# MCU.net
KiCad netlist of a schematic drawn in Altium Designer
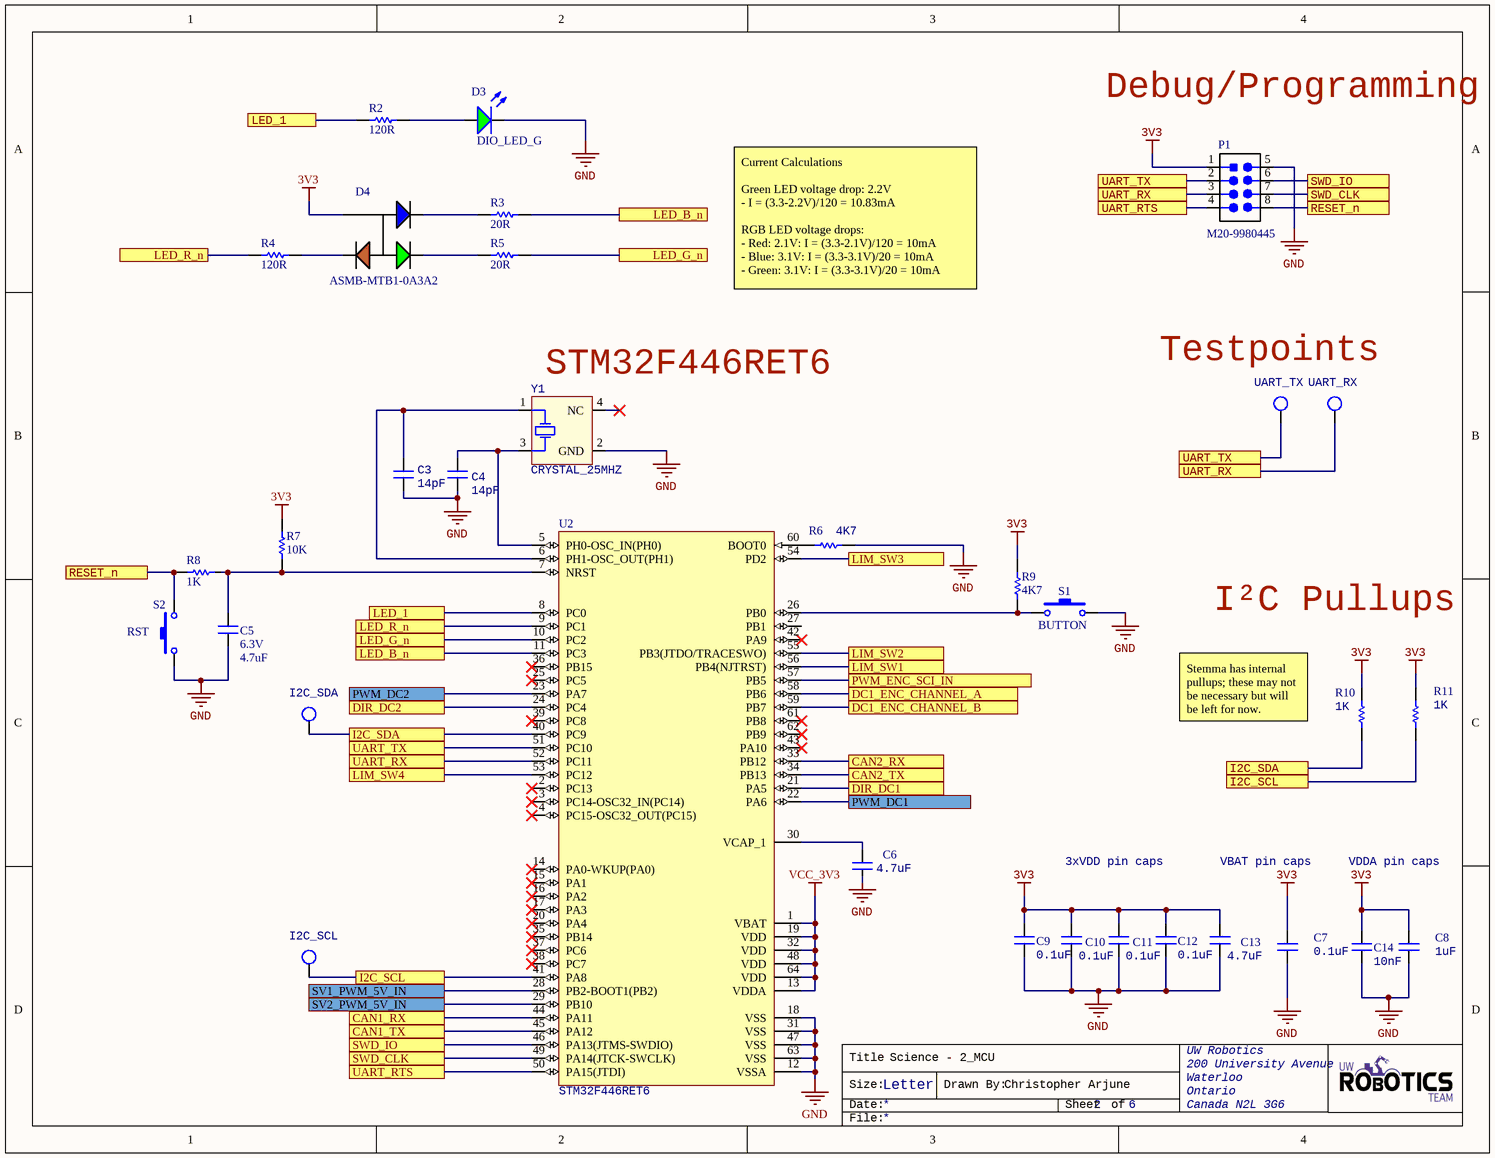
[diagram p0: MCU.SchDoc]

(export (version "E")
  (design (tool "Eeschema 10.0.6"))
  (components
    (comp (ref "C3")
      (value "14pF")
      (description "CAP CER 14PF 50V C0G/NP0 0603")
      (fields (field (name "TOLERANCE") "5%") (field (name "Comment") "CAP_14pF_50V_0603"))
      (libsource (lib "UWRT_Schematic_Library_2020") (part "CAP_14pF_50V_0603"))
    )
    (comp (ref "C4")
      (value "14pF")
      (description "CAP CER 14PF 50V C0G/NP0 0603")
      (fields (field (name "TOLERANCE") "5%") (field (name "Comment") "CAP_14pF_50V_0603"))
      (libsource (lib "UWRT_Schematic_Library_2020") (part "CAP_14pF_50V_0603"))
    )
    (comp (ref "C5")
      (value "4.7uF")
      (footprint "CAPC0603(1608)55_N")
      (description "CAP CER 4.7UF 6.3V X5R 0603")
      (fields (field (name "VOLTAGE RATING") "6.3V") (field (name "Comment") "CAP_4.7uF_0603"))
      (libsource (lib "UWRT_Schematic_Library_2020") (part "CAP_4.7uF_0603"))
    )
    (comp (ref "C6")
      (value "4.7uF")
      (footprint "CAPC0603(1608)55_N")
      (description "CAP CER 4.7UF 6.3V X5R 0603")
      (fields (field (name "MANUFACTURER") "Yageo") (field (name "MPN") "CC0603KRX5R5BB475"))
      (libsource (lib "UWRT_Schematic_Library_2020") (part "CAP_4.7uF_0603"))
    )
    (comp (ref "C7")
      (value "0.1uF")
      (footprint "CAPC0603(1608)55_N")
      (description "CAP CER 0.1UF 16V X7R 0603")
      (fields (field (name "MANUFACTURER") "Yageo") (field (name "MPN") "CC0603KRX7R7BB104"))
      (libsource (lib "UWRT_Schematic_Library_2020") (part "CAP_0.1uF_16V_0603"))
    )
    (comp (ref "C8")
      (value "1uF")
      (footprint "CAPC0603(1608)55_N")
      (description "CAP CER 1UF 16V Y5V 0603")
      (fields (field (name "MANUFACTURER") "Yageo") (field (name "MPN") "CC0603ZRY5V7BB105"))
      (libsource (lib "UWRT_Schematic_Library_2020") (part "CAP_1uF_16V_0603"))
    )
    (comp (ref "C9")
      (value "0.1uF")
      (footprint "CAPC0603(1608)55_N")
      (description "CAP CER 0.1UF 16V X7R 0603")
      (fields (field (name "MANUFACTURER") "Yageo") (field (name "MPN") "CC0603KRX7R7BB104"))
      (libsource (lib "UWRT_Schematic_Library_2020") (part "CAP_0.1uF_16V_0603"))
    )
    (comp (ref "C10")
      (value "0.1uF")
      (footprint "CAPC0603(1608)55_N")
      (description "CAP CER 0.1UF 16V X7R 0603")
      (fields (field (name "MANUFACTURER") "Yageo") (field (name "MPN") "CC0603KRX7R7BB104"))
      (libsource (lib "UWRT_Schematic_Library_2020") (part "CAP_0.1uF_16V_0603"))
    )
    (comp (ref "C11")
      (value "0.1uF")
      (footprint "CAPC0603(1608)55_N")
      (description "CAP CER 0.1UF 16V X7R 0603")
      (fields (field (name "MANUFACTURER") "Yageo") (field (name "MPN") "CC0603KRX7R7BB104"))
      (libsource (lib "UWRT_Schematic_Library_2020") (part "CAP_0.1uF_16V_0603"))
    )
    (comp (ref "C12")
      (value "0.1uF")
      (footprint "CAPC0603(1608)55_N")
      (description "CAP CER 0.1UF 16V X7R 0603")
      (fields (field (name "MANUFACTURER") "Yageo") (field (name "MPN") "CC0603KRX7R7BB104"))
      (libsource (lib "UWRT_Schematic_Library_2020") (part "CAP_0.1uF_16V_0603"))
    )
    (comp (ref "C13")
      (value "4.7uF")
      (footprint "CAPC0603(1608)55_N")
      (description "CAP CER 4.7UF 6.3V X5R 0603")
      (fields (field (name "MANUFACTURER") "Yageo") (field (name "MPN") "CC0603KRX5R5BB475"))
      (libsource (lib "UWRT_Schematic_Library_2020") (part "CAP_4.7uF_0603"))
    )
    (comp (ref "C14")
      (value "10nF")
      (footprint "CAPC0603(1608)55_N")
      (description "CAP CER 10000PF 16V X7R 0603")
      (fields (field (name "MANUFACTURER") "Yageo") (field (name "MPN") "CC0603KRX7R7BB103"))
      (libsource (lib "UWRT_Schematic_Library_2020") (part "CAP_10nF_0603"))
    )
    (comp (ref "D3")
      (value "DIO_LED_G")
      (footprint "LED_0805_LINE")
      (description "LED GREEN DIFFUSED 0805 SMD")
      (fields (field (name "MANUFACTURER") "OSRAM") (field (name "MPN") "LG R971-KN-1"))
      (libsource (lib "UWRT_Schematic_Library_2020") (part "DIO_LED_G"))
    )
    (comp (ref "D4")
      (value "LED_RGB")
      (footprint "LED_RGB")
      (description "LED RGB DIFFUSED 4PLCC SMD")
      (fields (field (name "MANUFACTURER PART NUMBER 1") "ASMB-MTB1-0A3A2"))
      (libsource (lib "UWRT_Schematic_Library_2020") (part "LED_RGB"))
    )
    (comp (ref "I2C_SCL")
      (value "TESTPOINT_LOOP")
      (footprint "TESTPOINT_LOOP")
      (description "Loop testpoint through-hole pad")
      (fields (field (name "MANUFACTURER") "Keystone Electronics"))
      (libsource (lib "UWRT_Schematic_Library_2020") (part "TESTPOINT_LOOP"))
    )
    (comp (ref "I2C_SDA")
      (value "TESTPOINT_LOOP")
      (footprint "TESTPOINT_LOOP")
      (description "Loop testpoint through-hole pad")
      (fields (field (name "MANUFACTURER") "Keystone Electronics"))
      (libsource (lib "UWRT_Schematic_Library_2020") (part "TESTPOINT_LOOP"))
    )
    (comp (ref "P1")
      (value "HEADER 4X2")
      (footprint "HEADER_2X4")
      (description "CONN HEADER VERT 8POS 2.54MM")
      (fields (field (name "MANUFACTURER PART NUMBER 1") "M20-9980445"))
      (libsource (lib "UWRT_Schematic_Library_2020") (part "HEADER 4X2"))
    )
    (comp (ref "R2")
      (value "120R")
      (footprint "RESC0603(1608)_N")
      (description "RES SMD 120 OHM 5% 1/10W 0603")
      (fields (field (name "MANUFACTURER") "Yageo") (field (name "TOLERANCE") "5%"))
      (libsource (lib "UWRT_Schematic_Library_2020") (part "RES_120R_0603"))
    )
    (comp (ref "R3")
      (value "20R")
      (footprint "RESC0603(1608)_N")
      (description "RES SMD 20 OHM 5% 1/10W 0603")
      (fields (field (name "MANUFACTURER") "Yageo") (field (name "MPN") "RC0603JR-0720RL"))
      (libsource (lib "UWRT_Schematic_Library_2020") (part "RES_20R_0603"))
    )
    (comp (ref "R4")
      (value "120R")
      (footprint "RESC0603(1608)_N")
      (description "RES SMD 120 OHM 5% 1/10W 0603")
      (fields (field (name "MANUFACTURER") "Yageo") (field (name "MPN") "RC0603JR-07120RL"))
      (libsource (lib "UWRT_Schematic_Library_2020") (part "RES_120R_0603"))
    )
    (comp (ref "R5")
      (value "20R")
      (footprint "RESC0603(1608)_N")
      (description "RES SMD 20 OHM 5% 1/10W 0603")
      (fields (field (name "MANUFACTURER") "Yageo") (field (name "MPN") "RC0603JR-0720RL"))
      (libsource (lib "UWRT_Schematic_Library_2020") (part "RES_20R_0603"))
    )
    (comp (ref "R6")
      (value "4K7")
      (footprint "RESC0603(1608)_N")
      (description "RES SMD 4.7K OHM 5% 1/10W 0603")
      (fields (field (name "MANUFACTURER") "Yageo") (field (name "TOLERANCE") "5%"))
      (libsource (lib "UWRT_Schematic_Library_2020") (part "RES_4K7_0603"))
    )
    (comp (ref "R7")
      (value "10K")
      (footprint "RESC0603(1608)_N")
      (description "RES SMD 10K OHM 5% 1/10W 0603")
      (fields (field (name "TOLERANCE") "5%") (field (name "Comment") "RES_10K_0603"))
      (libsource (lib "UWRT_Schematic_Library_2020") (part "RES_10K_0603"))
    )
    (comp (ref "R8")
      (value "1K")
      (footprint "RESC0603(1608)_N")
      (description "RES SMD 1K OHM 5% 1/10W 0603")
      (fields (field (name "TOLERANCE") "5%") (field (name "Comment") "RES_1K_0603"))
      (libsource (lib "UWRT_Schematic_Library_2020") (part "RES_1K_0603"))
    )
    (comp (ref "R9")
      (value "4K7")
      (footprint "RESC0603(1608)_N")
      (description "RES SMD 4.7K OHM 5% 1/10W 0603")
      (fields (field (name "MANUFACTURER") "Yageo") (field (name "TOLERANCE") "5%"))
      (libsource (lib "UWRT_Schematic_Library_2020") (part "RES_4K7_0603"))
    )
    (comp (ref "R10")
      (value "1K")
      (footprint "RESC0603(1608)_N")
      (description "RES SMD 4.7K OHM 5% 1/10W 0603")
      (fields (field (name "MANUFACTURER") "Yageo") (field (name "TOLERANCE") "5%"))
      (libsource (lib "UWRT_Schematic_Library_2020") (part "RES_4K7_0603"))
    )
    (comp (ref "R11")
      (value "1K")
      (footprint "RESC0603(1608)_N")
      (description "RES SMD 4.7K OHM 5% 1/10W 0603")
      (fields (field (name "MANUFACTURER") "Yageo") (field (name "TOLERANCE") "5%"))
      (libsource (lib "UWRT_Schematic_Library_2020") (part "RES_4K7_0603"))
    )
    (comp (ref "S1")
      (value "BUTTON")
      (footprint "B3U-1100P")
      (description "Tactile Switch (Grey)")
      (fields (field (name "MPN") "B3U-1100P") (field (name "MANUFACTURER") "Omron Electronics Inc-EMC Div"))
      (libsource (lib "UWRT_Schematic_Library_2020") (part "SW_TACTILE"))
    )
    (comp (ref "S2")
      (value "RST")
      (footprint "PTS830GM140")
      (description "Power Switch (Red)")
      (fields (field (name "MPN") "PTS830GM140 SMTR LFS") (field (name "MANUFACTURER") "C&K"))
      (libsource (lib "UWRT_Schematic_Library_2020") (part "SW_PWR"))
    )
    (comp (ref "U2")
      (value "STM32F446RET6")
      (footprint "STM-LQFP64_L")
      (libsource (lib "UWRT_Schematic_Library_2020") (part "MCU_STM32F446RET6"))
    )
    (comp (ref "UART_RX")
      (value "TESTPOINT_LOOP")
      (footprint "TESTPOINT_LOOP")
      (description "Loop testpoint through-hole pad")
      (fields (field (name "MANUFACTURER") "Keystone Electronics"))
      (libsource (lib "UWRT_Schematic_Library_2020") (part "TESTPOINT_LOOP"))
    )
    (comp (ref "UART_TX")
      (value "TESTPOINT_LOOP")
      (footprint "TESTPOINT_LOOP")
      (description "Loop testpoint through-hole pad")
      (fields (field (name "MANUFACTURER") "Keystone Electronics"))
      (libsource (lib "UWRT_Schematic_Library_2020") (part "TESTPOINT_LOOP"))
    )
    (comp (ref "Y1")
      (value "CRYSTAL_25MHZ")
      (description "CRYSTAL 25.0000MHZ 12PF SMD")
      (libsource (lib "UWRT_Schematic_Library_2020") (part "CRYSTAL_25MHZ"))
    )
  )
  (nets
    (net (code "1") (name "/CAN1_RX") (class "Default")
      (node (ref "U2") (pin "44") (pinfunction "PA11_44") (pintype "bidirectional"))
    )
    (net (code "2") (name "/CAN1_TX") (class "Default")
      (node (ref "U2") (pin "45") (pinfunction "PA12_45") (pintype "bidirectional"))
    )
    (net (code "3") (name "/CAN2_RX") (class "Default")
      (node (ref "U2") (pin "33") (pinfunction "PB12_33") (pintype "bidirectional"))
    )
    (net (code "4") (name "/CAN2_TX") (class "Default")
      (node (ref "U2") (pin "34") (pinfunction "PB13_34") (pintype "bidirectional"))
    )
    (net (code "5") (name "/DC1_ENC_CHANNEL_A") (class "Default")
      (node (ref "U2") (pin "58") (pinfunction "PB6_58") (pintype "bidirectional"))
    )
    (net (code "6") (name "/DC1_ENC_CHANNEL_B") (class "Default")
      (node (ref "U2") (pin "59") (pinfunction "PB7_59") (pintype "bidirectional"))
    )
    (net (code "7") (name "/DIR_DC1") (class "Default")
      (node (ref "U2") (pin "21") (pinfunction "PA5_21") (pintype "bidirectional"))
    )
    (net (code "8") (name "/DIR_DC2") (class "Default")
      (node (ref "U2") (pin "24") (pinfunction "PC4_24") (pintype "bidirectional"))
    )
    (net (code "9") (name "/I2C_SCL") (class "Default")
      (node (ref "I2C_SCL") (pin "1") (pintype "passive"))
      (node (ref "R11") (pin "1") (pinfunction "1_1") (pintype "passive"))
      (node (ref "U2") (pin "41") (pinfunction "PA8_41") (pintype "bidirectional"))
    )
    (net (code "10") (name "/I2C_SDA") (class "Default")
      (node (ref "I2C_SDA") (pin "1") (pintype "passive"))
      (node (ref "R10") (pin "1") (pinfunction "1_1") (pintype "passive"))
      (node (ref "U2") (pin "40") (pinfunction "PC9_40") (pintype "bidirectional"))
    )
    (net (code "11") (name "/LED_1") (class "Default")
      (node (ref "R2") (pin "1") (pinfunction "1_1") (pintype "passive"))
      (node (ref "U2") (pin "8") (pinfunction "PC0_8") (pintype "bidirectional"))
    )
    (net (code "12") (name "/LED_B_n") (class "Default")
      (node (ref "R3") (pin "2") (pinfunction "2_2") (pintype "passive"))
      (node (ref "U2") (pin "11") (pinfunction "PC3_11") (pintype "bidirectional"))
    )
    (net (code "13") (name "/LED_G_n") (class "Default")
      (node (ref "R5") (pin "2") (pinfunction "2_2") (pintype "passive"))
      (node (ref "U2") (pin "10") (pinfunction "PC2_10") (pintype "bidirectional"))
    )
    (net (code "14") (name "/LED_R_n") (class "Default")
      (node (ref "R4") (pin "1") (pinfunction "1_1") (pintype "passive"))
      (node (ref "U2") (pin "9") (pinfunction "PC1_9") (pintype "bidirectional"))
    )
    (net (code "15") (name "/LIM_SW1") (class "Default")
      (node (ref "U2") (pin "56") (pinfunction "PB4(NJTRST)_56") (pintype "bidirectional"))
    )
    (net (code "16") (name "/LIM_SW2") (class "Default")
      (node (ref "U2") (pin "55") (pinfunction "PB3(JTDO/TRACESWO)_55") (pintype "bidirectional"))
    )
    (net (code "17") (name "/LIM_SW3") (class "Default")
      (node (ref "U2") (pin "54") (pinfunction "PD2_54") (pintype "bidirectional"))
    )
    (net (code "18") (name "/LIM_SW4") (class "Default")
      (node (ref "U2") (pin "53") (pinfunction "PC12_53") (pintype "bidirectional"))
    )
    (net (code "19") (name "/PWM_DC1") (class "Default")
      (node (ref "U2") (pin "22") (pinfunction "PA6_22") (pintype "bidirectional"))
    )
    (net (code "20") (name "/PWM_DC2") (class "Default")
      (node (ref "U2") (pin "23") (pinfunction "PA7_23") (pintype "bidirectional"))
    )
    (net (code "21") (name "/PWM_ENC_SCI_IN") (class "Default")
      (node (ref "U2") (pin "57") (pinfunction "PB5_57") (pintype "bidirectional"))
    )
    (net (code "22") (name "/RESET_n") (class "Default")
      (node (ref "P1") (pin "8") (pinfunction "4_8") (pintype "passive"))
      (node (ref "R8") (pin "1") (pinfunction "1_1") (pintype "passive"))
      (node (ref "S2") (pin "2") (pinfunction "2_2") (pintype "passive"))
    )
    (net (code "23") (name "/SV1_PWM_5V_IN") (class "Default")
      (node (ref "U2") (pin "28") (pinfunction "PB2-BOOT1(PB2)_28") (pintype "bidirectional"))
    )
    (net (code "24") (name "/SV2_PWM_5V_IN") (class "Default")
      (node (ref "U2") (pin "29") (pinfunction "PB10_29") (pintype "bidirectional"))
    )
    (net (code "25") (name "/SWD_CLK") (class "Default")
      (node (ref "P1") (pin "7") (pinfunction "3_7") (pintype "passive"))
      (node (ref "U2") (pin "49") (pinfunction "PA14(JTCK-SWCLK)_49") (pintype "bidirectional"))
    )
    (net (code "26") (name "/SWD_IO") (class "Default")
      (node (ref "P1") (pin "6") (pinfunction "2_6") (pintype "passive"))
      (node (ref "U2") (pin "46") (pinfunction "PA13(JTMS-SWDIO)_46") (pintype "bidirectional"))
    )
    (net (code "27") (name "/UART_RTS") (class "Default")
      (node (ref "P1") (pin "4") (pinfunction "4_4") (pintype "passive"))
      (node (ref "U2") (pin "50") (pinfunction "PA15(JTDI)_50") (pintype "bidirectional"))
    )
    (net (code "28") (name "/UART_RX") (class "Default")
      (node (ref "P1") (pin "3") (pinfunction "3_3") (pintype "passive"))
      (node (ref "U2") (pin "52") (pinfunction "PC11_52") (pintype "bidirectional"))
      (node (ref "UART_RX") (pin "1") (pintype "passive"))
    )
    (net (code "29") (name "/UART_TX") (class "Default")
      (node (ref "P1") (pin "2") (pinfunction "2_2") (pintype "passive"))
      (node (ref "U2") (pin "51") (pinfunction "PC10_51") (pintype "bidirectional"))
      (node (ref "UART_TX") (pin "1") (pintype "passive"))
    )
    (net (code "30") (name "3V3") (class "Default")
      (node (ref "C10") (pin "2") (pinfunction "2_2") (pintype "passive"))
      (node (ref "C11") (pin "2") (pinfunction "2_2") (pintype "passive"))
      (node (ref "C12") (pin "2") (pinfunction "2_2") (pintype "passive"))
      (node (ref "C13") (pin "2") (pinfunction "2_2") (pintype "passive"))
      (node (ref "C14") (pin "2") (pinfunction "2_2") (pintype "passive"))
      (node (ref "C7") (pin "2") (pinfunction "2_2") (pintype "passive"))
      (node (ref "C8") (pin "2") (pinfunction "2_2") (pintype "passive"))
      (node (ref "C9") (pin "2") (pinfunction "2_2") (pintype "passive"))
      (node (ref "D4") (pin "4") (pinfunction "9_4") (pintype "passive"))
      (node (ref "P1") (pin "1") (pinfunction "VCC_1") (pintype "passive"))
      (node (ref "R10") (pin "2") (pinfunction "2_2") (pintype "passive"))
      (node (ref "R11") (pin "2") (pinfunction "2_2") (pintype "passive"))
      (node (ref "R7") (pin "2") (pinfunction "2_2") (pintype "passive"))
      (node (ref "R9") (pin "1") (pinfunction "1_1") (pintype "passive"))
    )
    (net (code "31") (name "GND") (class "Default")
      (node (ref "C10") (pin "1") (pinfunction "1_1") (pintype "passive"))
      (node (ref "C11") (pin "1") (pinfunction "1_1") (pintype "passive"))
      (node (ref "C12") (pin "1") (pinfunction "1_1") (pintype "passive"))
      (node (ref "C13") (pin "1") (pinfunction "1_1") (pintype "passive"))
      (node (ref "C14") (pin "1") (pinfunction "1_1") (pintype "passive"))
      (node (ref "C3") (pin "1") (pinfunction "1_1") (pintype "passive"))
      (node (ref "C4") (pin "1") (pinfunction "1_1") (pintype "passive"))
      (node (ref "C5") (pin "2") (pinfunction "2_2") (pintype "passive"))
      (node (ref "C6") (pin "1") (pinfunction "1_1") (pintype "passive"))
      (node (ref "C7") (pin "1") (pinfunction "1_1") (pintype "passive"))
      (node (ref "C8") (pin "1") (pinfunction "1_1") (pintype "passive"))
      (node (ref "C9") (pin "1") (pinfunction "1_1") (pintype "passive"))
      (node (ref "D3") (pin "2") (pinfunction "K_2") (pintype "passive"))
      (node (ref "P1") (pin "5") (pinfunction "GND_5") (pintype "passive"))
      (node (ref "R6") (pin "1") (pinfunction "1_1") (pintype "passive"))
      (node (ref "S1") (pin "2") (pinfunction "2_2") (pintype "passive"))
      (node (ref "S2") (pin "1") (pinfunction "1_1") (pintype "passive"))
      (node (ref "U2") (pin "12") (pinfunction "VSSA_12") (pintype "power_in"))
      (node (ref "U2") (pin "18") (pinfunction "VSS_18") (pintype "power_in"))
      (node (ref "U2") (pin "31") (pinfunction "VSS_31") (pintype "power_in"))
      (node (ref "U2") (pin "47") (pinfunction "VSS_47") (pintype "power_in"))
      (node (ref "U2") (pin "63") (pinfunction "VSS_63") (pintype "power_in"))
      (node (ref "Y1") (pin "2") (pinfunction "GND_2") (pintype "power_in"))
    )
    (net (code "32") (name "Net-(D3-A)") (class "Default")
      (node (ref "D3") (pin "1") (pinfunction "A_1") (pintype "passive"))
      (node (ref "R2") (pin "2") (pinfunction "2_2") (pintype "passive"))
    )
    (net (code "33") (name "Net-(D4-10)") (class "Default")
      (node (ref "D4") (pin "3") (pinfunction "10_3") (pintype "passive"))
      (node (ref "R3") (pin "1") (pinfunction "1_1") (pintype "passive"))
    )
    (net (code "34") (name "Net-(D4-11)") (class "Default")
      (node (ref "D4") (pin "1") (pinfunction "11_1") (pintype "passive"))
      (node (ref "R4") (pin "2") (pinfunction "2_2") (pintype "passive"))
    )
    (net (code "35") (name "Net-(D4-12)") (class "Default")
      (node (ref "D4") (pin "2") (pinfunction "12_2") (pintype "passive"))
      (node (ref "R5") (pin "1") (pinfunction "1_1") (pintype "passive"))
    )
    (net (code "36") (name "Net-(U2-BOOT0)") (class "Default")
      (node (ref "R6") (pin "2") (pinfunction "2_2") (pintype "passive"))
      (node (ref "U2") (pin "60") (pinfunction "BOOT0_60") (pintype "input"))
    )
    (net (code "37") (name "Net-(U2-NRST)") (class "Default")
      (node (ref "C5") (pin "1") (pinfunction "1_1") (pintype "passive"))
      (node (ref "R7") (pin "1") (pinfunction "1_1") (pintype "passive"))
      (node (ref "R8") (pin "2") (pinfunction "2_2") (pintype "passive"))
      (node (ref "U2") (pin "7") (pinfunction "NRST_7") (pintype "bidirectional"))
    )
    (net (code "38") (name "Net-(U2-PB0)") (class "Default")
      (node (ref "R9") (pin "2") (pinfunction "2_2") (pintype "passive"))
      (node (ref "S1") (pin "1") (pinfunction "1_1") (pintype "passive"))
      (node (ref "U2") (pin "26") (pinfunction "PB0_26") (pintype "bidirectional"))
    )
    (net (code "39") (name "Net-(U2-PH0-OSC_IN(PH0))") (class "Default")
      (node (ref "C4") (pin "2") (pinfunction "2_2") (pintype "passive"))
      (node (ref "U2") (pin "5") (pinfunction "PH0-OSC_IN(PH0)_5") (pintype "bidirectional"))
      (node (ref "Y1") (pin "3") (pinfunction "HOT_3") (pintype "passive"))
    )
    (net (code "40") (name "Net-(U2-PH1-OSC_OUT(PH1))") (class "Default")
      (node (ref "C3") (pin "2") (pinfunction "2_2") (pintype "passive"))
      (node (ref "U2") (pin "6") (pinfunction "PH1-OSC_OUT(PH1)_6") (pintype "bidirectional"))
      (node (ref "Y1") (pin "1") (pinfunction "HOT_1") (pintype "passive"))
    )
    (net (code "41") (name "Net-(U2-VCAP_1)") (class "Default")
      (node (ref "C6") (pin "2") (pinfunction "2_2") (pintype "passive"))
      (node (ref "U2") (pin "30") (pinfunction "VCAP_1_30") (pintype "passive"))
    )
    (net (code "42") (name "VCC_3V3") (class "Default")
      (node (ref "U2") (pin "1") (pinfunction "VBAT_1") (pintype "power_in"))
      (node (ref "U2") (pin "13") (pinfunction "VDDA_13") (pintype "power_in"))
      (node (ref "U2") (pin "19") (pinfunction "VDD_19") (pintype "power_in"))
      (node (ref "U2") (pin "32") (pinfunction "VDD_32") (pintype "power_in"))
      (node (ref "U2") (pin "48") (pinfunction "VDD_48") (pintype "power_in"))
      (node (ref "U2") (pin "64") (pinfunction "VDD_64") (pintype "power_in"))
    )
    (net (code "43") (name "unconnected-(U2-PA0-WKUP(PA0)-Pad14)") (class "Default")
      (node (ref "U2") (pin "14") (pinfunction "PA0-WKUP(PA0)_14") (pintype "bidirectional+no_connect"))
    )
    (net (code "44") (name "unconnected-(U2-PA1-Pad15)") (class "Default")
      (node (ref "U2") (pin "15") (pinfunction "PA1_15") (pintype "bidirectional+no_connect"))
    )
    (net (code "45") (name "unconnected-(U2-PA2-Pad16)") (class "Default")
      (node (ref "U2") (pin "16") (pinfunction "PA2_16") (pintype "bidirectional+no_connect"))
    )
    (net (code "46") (name "unconnected-(U2-PA3-Pad17)") (class "Default")
      (node (ref "U2") (pin "17") (pinfunction "PA3_17") (pintype "bidirectional+no_connect"))
    )
    (net (code "47") (name "unconnected-(U2-PA4-Pad20)") (class "Default")
      (node (ref "U2") (pin "20") (pinfunction "PA4_20") (pintype "bidirectional+no_connect"))
    )
    (net (code "48") (name "unconnected-(U2-PA9-Pad42)") (class "Default")
      (node (ref "U2") (pin "42") (pinfunction "PA9_42") (pintype "bidirectional+no_connect"))
    )
    (net (code "49") (name "unconnected-(U2-PA10-Pad43)") (class "Default")
      (node (ref "U2") (pin "43") (pinfunction "PA10_43") (pintype "bidirectional+no_connect"))
    )
    (net (code "50") (name "unconnected-(U2-PB1-Pad27)") (class "Default")
      (node (ref "U2") (pin "27") (pinfunction "PB1_27") (pintype "bidirectional"))
    )
    (net (code "51") (name "unconnected-(U2-PB8-Pad61)") (class "Default")
      (node (ref "U2") (pin "61") (pinfunction "PB8_61") (pintype "bidirectional+no_connect"))
    )
    (net (code "52") (name "unconnected-(U2-PB9-Pad62)") (class "Default")
      (node (ref "U2") (pin "62") (pinfunction "PB9_62") (pintype "bidirectional+no_connect"))
    )
    (net (code "53") (name "unconnected-(U2-PB14-Pad35)") (class "Default")
      (node (ref "U2") (pin "35") (pinfunction "PB14_35") (pintype "bidirectional+no_connect"))
    )
    (net (code "54") (name "unconnected-(U2-PB15-Pad36)") (class "Default")
      (node (ref "U2") (pin "36") (pinfunction "PB15_36") (pintype "bidirectional+no_connect"))
    )
    (net (code "55") (name "unconnected-(U2-PC5-Pad25)") (class "Default")
      (node (ref "U2") (pin "25") (pinfunction "PC5_25") (pintype "bidirectional+no_connect"))
    )
    (net (code "56") (name "unconnected-(U2-PC6-Pad37)") (class "Default")
      (node (ref "U2") (pin "37") (pinfunction "PC6_37") (pintype "bidirectional+no_connect"))
    )
    (net (code "57") (name "unconnected-(U2-PC7-Pad38)") (class "Default")
      (node (ref "U2") (pin "38") (pinfunction "PC7_38") (pintype "bidirectional+no_connect"))
    )
    (net (code "58") (name "unconnected-(U2-PC8-Pad39)") (class "Default")
      (node (ref "U2") (pin "39") (pinfunction "PC8_39") (pintype "bidirectional+no_connect"))
    )
    (net (code "59") (name "unconnected-(U2-PC13-Pad2)") (class "Default")
      (node (ref "U2") (pin "2") (pinfunction "PC13_2") (pintype "bidirectional+no_connect"))
    )
    (net (code "60") (name "unconnected-(U2-PC14-OSC32_IN(PC14)-Pad3)") (class "Default")
      (node (ref "U2") (pin "3") (pinfunction "PC14-OSC32_IN(PC14)_3") (pintype "bidirectional+no_connect"))
    )
    (net (code "61") (name "unconnected-(U2-PC15-OSC32_OUT(PC15)-Pad4)") (class "Default")
      (node (ref "U2") (pin "4") (pinfunction "PC15-OSC32_OUT(PC15)_4") (pintype "bidirectional+no_connect"))
    )
    (net (code "62") (name "unconnected-(Y1-NC-Pad4)") (class "Default")
      (node (ref "Y1") (pin "4") (pinfunction "NC_4") (pintype "passive+no_connect"))
    )
  )
)
